# Brain-PCB_Master_RigFlex-test.net
KiCad netlist of a schematic drawn in Altium Designer
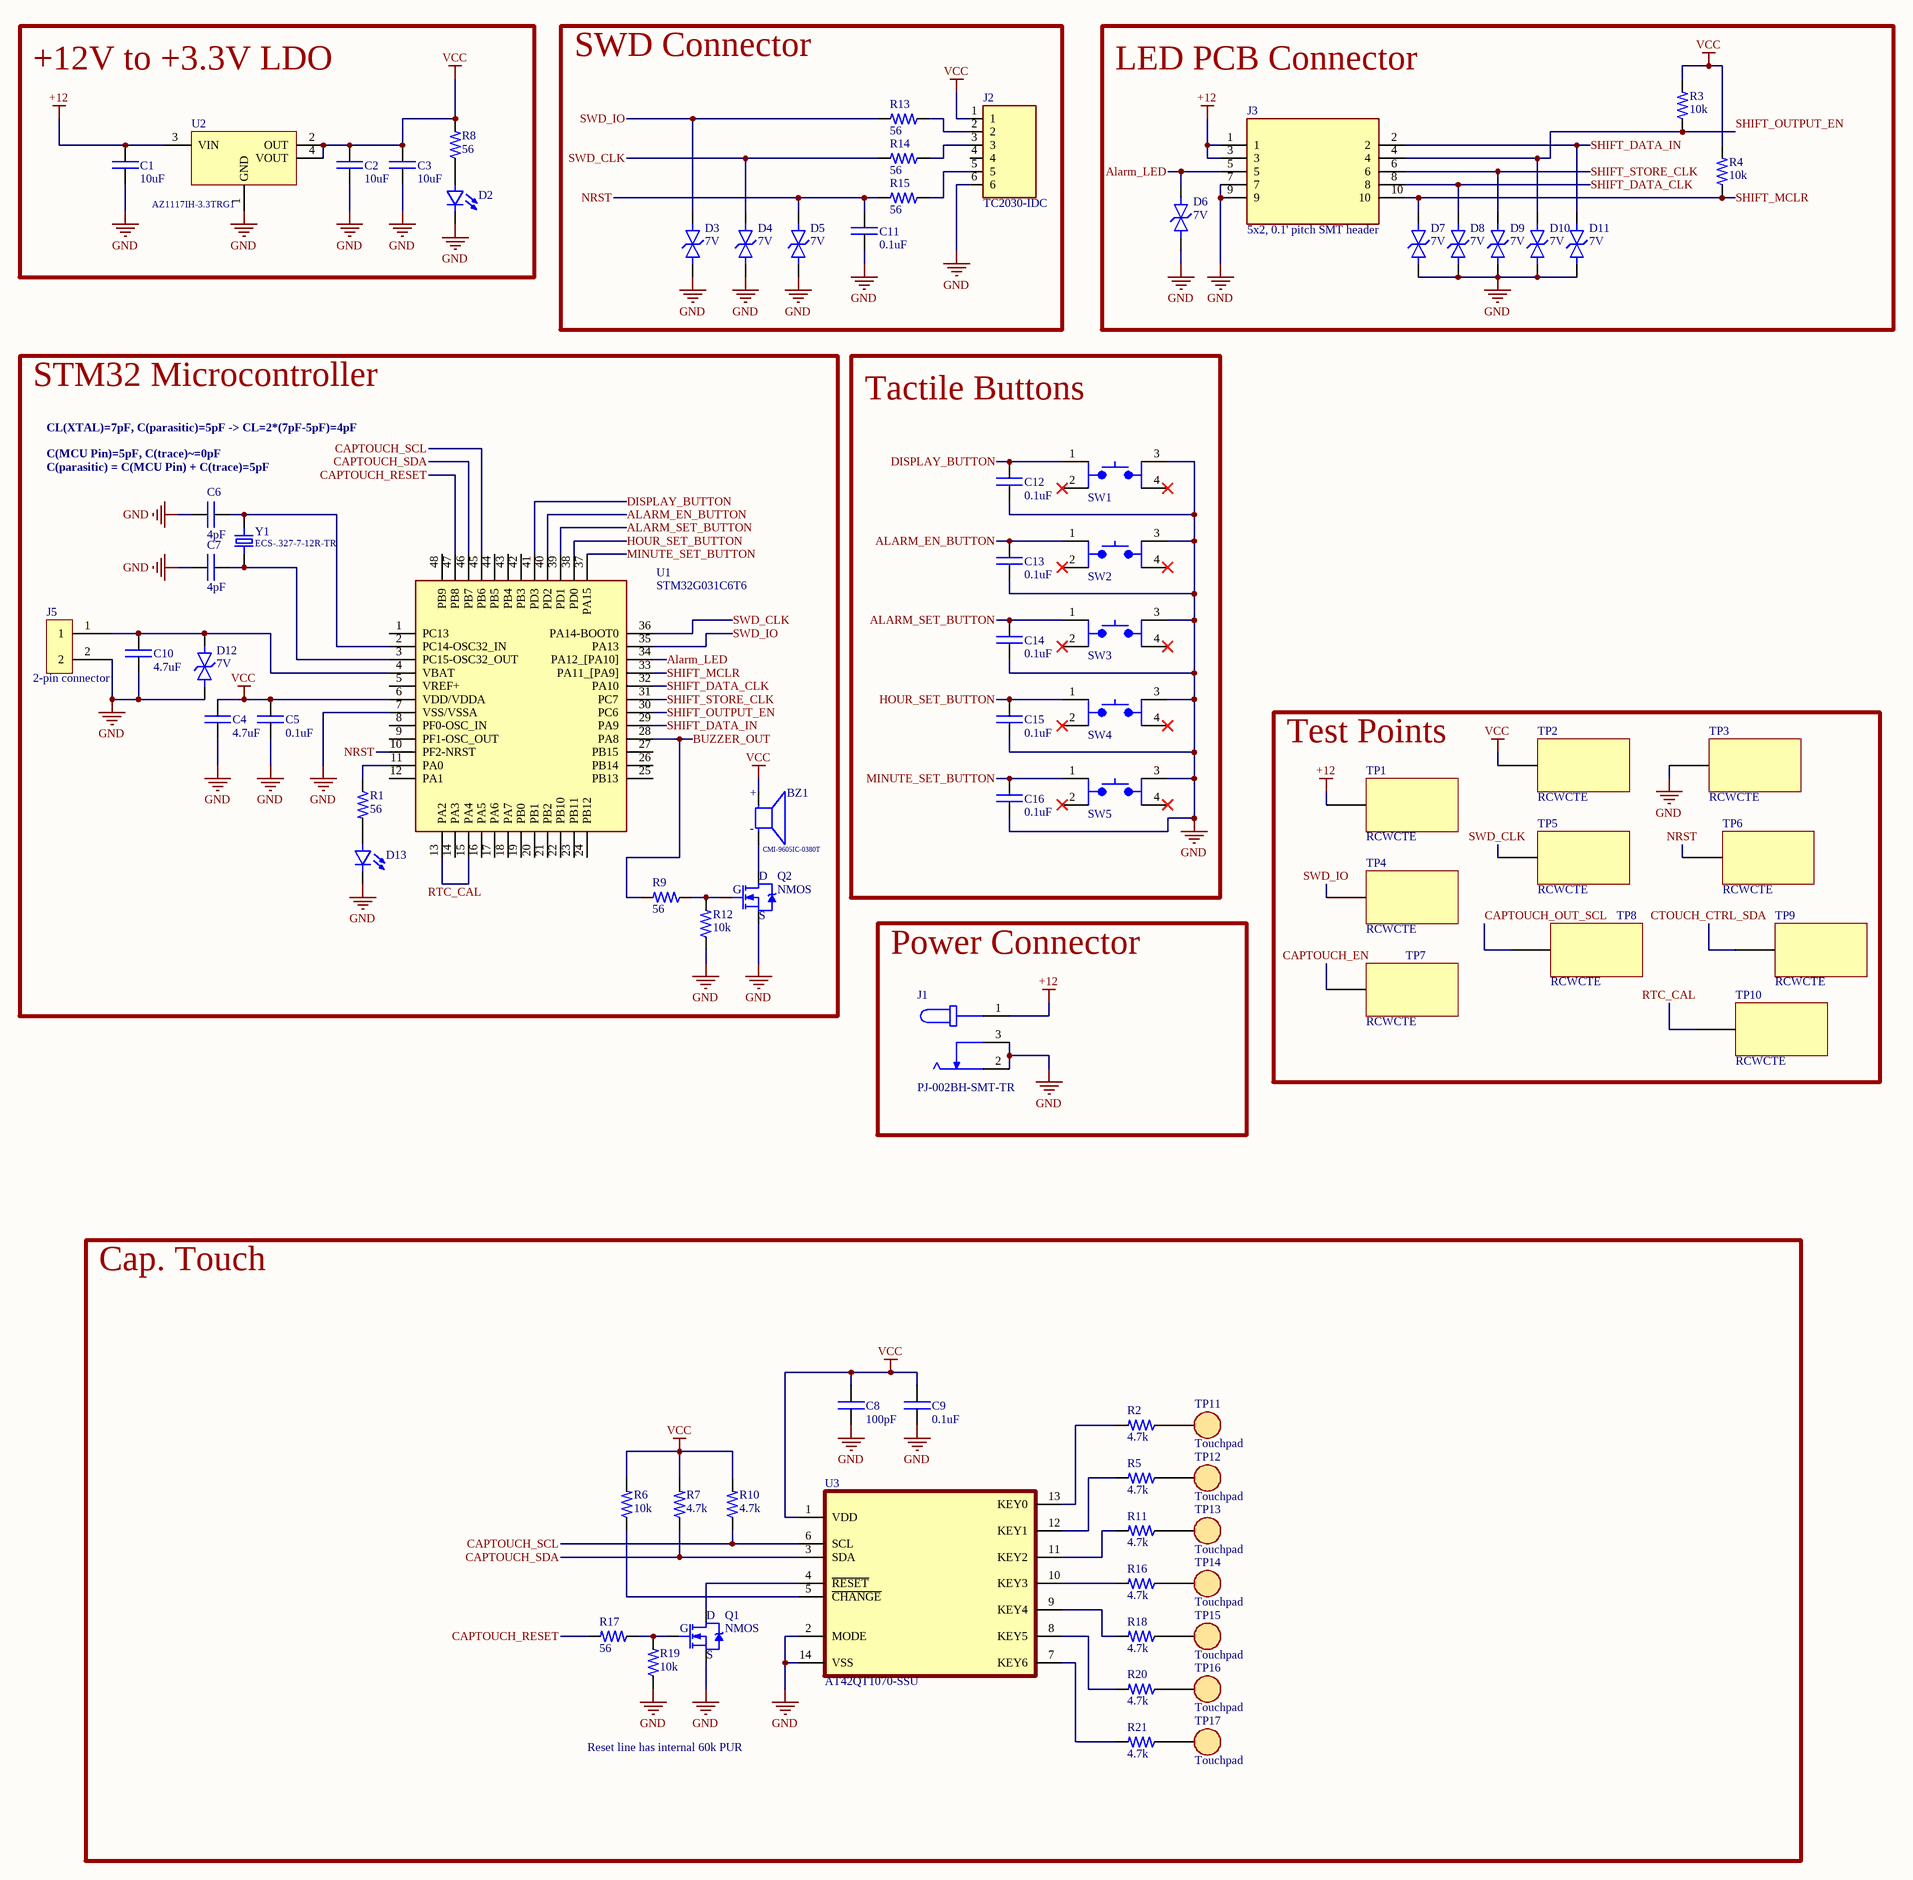
[diagram p0: Brain-PCB_Master_RigFlex-test.SchDoc]

(export (version "E")
  (design (tool "Eeschema 10.0.6"))
  (components
    (comp (ref "BZ1")
      (value "CMI-9605IC-0380T")
      (footprint "sinking-clock:CUI_CMI-9605IC-0380T")
      (description "MAGNETIC BUZZER INDICATOR")
      (fields (field (name "MFR") "CUI Devices"))
      (libsource (lib "sinking-clock") (part "CMI-9605IC-0380T"))
    )
    (comp (ref "C1")
      (value "10uF")
      (footprint "sinking-clock:0402C")
      (description "Capaicitor")
      (fields (field (name "MFR") "KYOCERA AVX") (field (name "Comment") "CAP"))
      (libsource (lib "sinking-clock") (part "CAP"))
    )
    (comp (ref "C2")
      (value "10uF")
      (footprint "sinking-clock:0402C")
      (description "Capaicitor")
      (fields (field (name "MFR") "KYOCERA AVX") (field (name "Comment") "CAP"))
      (libsource (lib "sinking-clock") (part "CAP"))
    )
    (comp (ref "C3")
      (value "10uF")
      (footprint "sinking-clock:0402C")
      (description "Capaicitor")
      (fields (field (name "MFR") "KYOCERA AVX") (field (name "Comment") "CAP"))
      (libsource (lib "sinking-clock") (part "CAP"))
    )
    (comp (ref "C4")
      (value "4.7uF")
      (footprint "sinking-clock:0402C")
      (description "Capaicitor")
      (fields (field (name "MFR") "Samsung Electro-Mechanics") (field (name "Comment") "CAP"))
      (libsource (lib "sinking-clock") (part "CAP"))
    )
    (comp (ref "C5")
      (value "0.1uF")
      (footprint "sinking-clock:0402C")
      (description "Capaicitor")
      (fields (field (name "MFR") "Samsung Electro-Mechanics") (field (name "Comment") "CAP"))
      (libsource (lib "sinking-clock") (part "CAP"))
    )
    (comp (ref "C6")
      (value "4pF")
      (footprint "sinking-clock:0402C")
      (description "Capaicitor")
      (fields (field (name "Comment") "CAP"))
      (libsource (lib "sinking-clock") (part "CAP"))
    )
    (comp (ref "C7")
      (value "4pF")
      (footprint "sinking-clock:0402C")
      (description "Capaicitor")
      (fields (field (name "Comment") "CAP"))
      (libsource (lib "sinking-clock") (part "CAP"))
    )
    (comp (ref "C8")
      (value "100pF")
      (footprint "sinking-clock:0402C")
      (description "Capaicitor")
      (fields (field (name "Comment") "CAP"))
      (libsource (lib "sinking-clock") (part "CAP"))
    )
    (comp (ref "C9")
      (value "0.1uF")
      (footprint "sinking-clock:0402C")
      (description "Capaicitor")
      (fields (field (name "MFR") "Samsung Electro-Mechanics") (field (name "Comment") "CAP"))
      (libsource (lib "sinking-clock") (part "CAP"))
    )
    (comp (ref "C10")
      (value "4.7uF")
      (footprint "sinking-clock:0402C")
      (description "Capaicitor")
      (fields (field (name "MFR") "Samsung Electro-Mechanics") (field (name "Comment") "CAP"))
      (libsource (lib "sinking-clock") (part "CAP"))
    )
    (comp (ref "C11")
      (value "0.1uF")
      (footprint "sinking-clock:0402C")
      (description "Capaicitor")
      (fields (field (name "MFR") "Samsung Electro-Mechanics") (field (name "Comment") "CAP"))
      (libsource (lib "sinking-clock") (part "CAP"))
    )
    (comp (ref "C12")
      (value "0.1uF")
      (footprint "sinking-clock:0402C")
      (description "Capaicitor")
      (fields (field (name "MFR") "Samsung Electro-Mechanics") (field (name "Comment") "CAP"))
      (libsource (lib "sinking-clock") (part "CAP"))
    )
    (comp (ref "C13")
      (value "0.1uF")
      (footprint "sinking-clock:0402C")
      (description "Capaicitor")
      (fields (field (name "MFR") "Samsung Electro-Mechanics") (field (name "Comment") "CAP"))
      (libsource (lib "sinking-clock") (part "CAP"))
    )
    (comp (ref "C14")
      (value "0.1uF")
      (footprint "sinking-clock:0402C")
      (description "Capaicitor")
      (fields (field (name "MFR") "Samsung Electro-Mechanics") (field (name "Comment") "CAP"))
      (libsource (lib "sinking-clock") (part "CAP"))
    )
    (comp (ref "C15")
      (value "0.1uF")
      (footprint "sinking-clock:0402C")
      (description "Capaicitor")
      (fields (field (name "MFR") "Samsung Electro-Mechanics") (field (name "Comment") "CAP"))
      (libsource (lib "sinking-clock") (part "CAP"))
    )
    (comp (ref "C16")
      (value "0.1uF")
      (footprint "sinking-clock:0402C")
      (description "Capaicitor")
      (fields (field (name "MFR") "Samsung Electro-Mechanics") (field (name "Comment") "CAP"))
      (libsource (lib "sinking-clock") (part "CAP"))
    )
    (comp (ref "D2")
      (value "LED - single")
      (footprint "sinking-clock:LED - 0603")
      (description "LED")
      (fields (field (name "MFR") "Dialight"))
      (libsource (lib "sinking-clock") (part "LED - single"))
    )
    (comp (ref "D3")
      (value "7V")
      (footprint "sinking-clock:DESD3V3S1BL-7B")
      (fields (field (name "MFR") "Diodes Incorporated"))
      (libsource (lib "sinking-clock") (part "TVS Diode Bi"))
    )
    (comp (ref "D4")
      (value "7V")
      (footprint "sinking-clock:DESD3V3S1BL-7B")
      (fields (field (name "MFR") "Diodes Incorporated"))
      (libsource (lib "sinking-clock") (part "TVS Diode Bi"))
    )
    (comp (ref "D5")
      (value "7V")
      (footprint "sinking-clock:DESD3V3S1BL-7B")
      (fields (field (name "MFR") "Diodes Incorporated"))
      (libsource (lib "sinking-clock") (part "TVS Diode Bi"))
    )
    (comp (ref "D6")
      (value "7V")
      (footprint "sinking-clock:DESD3V3S1BL-7B")
      (fields (field (name "MFR") "Diodes Incorporated"))
      (libsource (lib "sinking-clock") (part "TVS Diode Bi"))
    )
    (comp (ref "D7")
      (value "7V")
      (footprint "sinking-clock:DESD3V3S1BL-7B")
      (fields (field (name "MFR") "Diodes Incorporated"))
      (libsource (lib "sinking-clock") (part "TVS Diode Bi"))
    )
    (comp (ref "D8")
      (value "7V")
      (footprint "sinking-clock:DESD3V3S1BL-7B")
      (fields (field (name "MFR") "Diodes Incorporated"))
      (libsource (lib "sinking-clock") (part "TVS Diode Bi"))
    )
    (comp (ref "D9")
      (value "7V")
      (footprint "sinking-clock:DESD3V3S1BL-7B")
      (fields (field (name "MFR") "Diodes Incorporated"))
      (libsource (lib "sinking-clock") (part "TVS Diode Bi"))
    )
    (comp (ref "D10")
      (value "7V")
      (footprint "sinking-clock:DESD3V3S1BL-7B")
      (fields (field (name "MFR") "Diodes Incorporated"))
      (libsource (lib "sinking-clock") (part "TVS Diode Bi"))
    )
    (comp (ref "D11")
      (value "7V")
      (footprint "sinking-clock:DESD3V3S1BL-7B")
      (fields (field (name "MFR") "Diodes Incorporated"))
      (libsource (lib "sinking-clock") (part "TVS Diode Bi"))
    )
    (comp (ref "D12")
      (value "7V")
      (footprint "sinking-clock:DESD3V3S1BL-7B")
      (fields (field (name "MFR") "Diodes Incorporated"))
      (libsource (lib "sinking-clock") (part "TVS Diode Bi"))
    )
    (comp (ref "D13")
      (value "LED - single")
      (footprint "sinking-clock:LED - 0603")
      (description "LED")
      (fields (field (name "MFR") "Dialight"))
      (libsource (lib "sinking-clock") (part "LED - single"))
    )
    (comp (ref "J1")
      (value "PJ-002BH-SMT-TR")
      (footprint "sinking-clock:PJ-002BH-SMT-TR")
      (description "2.5 mm Center Pin, 5.0 A, Right Angle, Surface Mount (SMT), Dc Power Jack Connector")
      (fields (field (name "MFR") "CUI Devices"))
      (libsource (lib "sinking-clock") (part "PJ-002BH-SMT-TR"))
    )
    (comp (ref "J2")
      (value "TC2030-IDC")
      (footprint "sinking-clock:TAG CONNECT TC2030IDC - NO 3D MODEL")
      (description "\"Plug of Nails\" POGO Pin connector")
      (fields (field (name "MFR") "Tag-Connect"))
      (libsource (lib "sinking-clock") (part "TC2030-IDC"))
    )
    (comp (ref "J3")
      (value "5x2, 0.1' pitch SMT header")
      (footprint "sinking-clock:5x2, 0.1' pitch SMT header")
      (description "CONN HEADER SMD 10POS 2.54MM")
      (fields (field (name "MFR") "CNC Tech"))
      (libsource (lib "sinking-clock") (part "5x2, 0.1' pitch SMT header"))
    )
    (comp (ref "J5")
      (value "2-pin connector")
      (footprint "sinking-clock:2-pos, 0.1\" TH header")
      (description "2-pos connector, 0.1\", TH, male")
      (libsource (lib "sinking-clock") (part "2-pin connector"))
    )
    (comp (ref "Q1")
      (value "NMOS")
      (footprint "sinking-clock:SOT-23")
      (description "N-Channel MOSFET")
      (fields (field (name "MFR") "Diodes Incorporated"))
      (libsource (lib "sinking-clock") (part "NMOS"))
    )
    (comp (ref "Q2")
      (value "NMOS")
      (footprint "sinking-clock:SOT-23")
      (description "N-Channel MOSFET")
      (fields (field (name "MFR") "Diodes Incorporated"))
      (libsource (lib "sinking-clock") (part "NMOS"))
    )
    (comp (ref "R1")
      (value "56")
      (footprint "sinking-clock:0402R")
      (description "Resistor")
      (fields (field (name "MFR") "YAGEO") (field (name "Comment") "RES"))
      (libsource (lib "sinking-clock") (part "RES"))
    )
    (comp (ref "R2")
      (value "4.7k")
      (footprint "sinking-clock:0402R")
      (description "Resistor")
      (fields (field (name "MFR") "YAGEO") (field (name "Comment") "RES"))
      (libsource (lib "sinking-clock") (part "RES"))
    )
    (comp (ref "R3")
      (value "10k")
      (footprint "sinking-clock:0402R")
      (description "Resistor")
      (fields (field (name "MFR") "YAGEO") (field (name "Comment") "RES"))
      (libsource (lib "sinking-clock") (part "RES"))
    )
    (comp (ref "R4")
      (value "10k")
      (footprint "sinking-clock:0402R")
      (description "Resistor")
      (fields (field (name "MFR") "YAGEO") (field (name "Comment") "RES"))
      (libsource (lib "sinking-clock") (part "RES"))
    )
    (comp (ref "R5")
      (value "4.7k")
      (footprint "sinking-clock:0402R")
      (description "Resistor")
      (fields (field (name "MFR") "YAGEO") (field (name "Comment") "RES"))
      (libsource (lib "sinking-clock") (part "RES"))
    )
    (comp (ref "R6")
      (value "10k")
      (footprint "sinking-clock:0402R")
      (description "Resistor")
      (fields (field (name "MFR") "YAGEO") (field (name "Comment") "RES"))
      (libsource (lib "sinking-clock") (part "RES"))
    )
    (comp (ref "R7")
      (value "4.7k")
      (footprint "sinking-clock:0402R")
      (description "Resistor")
      (fields (field (name "MFR") "YAGEO") (field (name "Comment") "RES"))
      (libsource (lib "sinking-clock") (part "RES"))
    )
    (comp (ref "R8")
      (value "56")
      (footprint "sinking-clock:0402R")
      (description "Resistor")
      (fields (field (name "MFR") "YAGEO") (field (name "Comment") "RES"))
      (libsource (lib "sinking-clock") (part "RES"))
    )
    (comp (ref "R9")
      (value "56")
      (footprint "sinking-clock:0402R")
      (description "Resistor")
      (fields (field (name "MFR") "YAGEO") (field (name "Comment") "RES"))
      (libsource (lib "sinking-clock") (part "RES"))
    )
    (comp (ref "R10")
      (value "4.7k")
      (footprint "sinking-clock:0402R")
      (description "Resistor")
      (fields (field (name "MFR") "YAGEO") (field (name "Comment") "RES"))
      (libsource (lib "sinking-clock") (part "RES"))
    )
    (comp (ref "R11")
      (value "4.7k")
      (footprint "sinking-clock:0402R")
      (description "Resistor")
      (fields (field (name "MFR") "YAGEO") (field (name "Comment") "RES"))
      (libsource (lib "sinking-clock") (part "RES"))
    )
    (comp (ref "R12")
      (value "10k")
      (footprint "sinking-clock:0402R")
      (description "Resistor")
      (fields (field (name "MFR") "YAGEO") (field (name "Comment") "RES"))
      (libsource (lib "sinking-clock") (part "RES"))
    )
    (comp (ref "R13")
      (value "56")
      (footprint "sinking-clock:0402R")
      (description "Resistor")
      (fields (field (name "MFR") "YAGEO") (field (name "Comment") "RES"))
      (libsource (lib "sinking-clock") (part "RES"))
    )
    (comp (ref "R14")
      (value "56")
      (footprint "sinking-clock:0402R")
      (description "Resistor")
      (fields (field (name "MFR") "YAGEO") (field (name "Comment") "RES"))
      (libsource (lib "sinking-clock") (part "RES"))
    )
    (comp (ref "R15")
      (value "56")
      (footprint "sinking-clock:0402R")
      (description "Resistor")
      (fields (field (name "MFR") "YAGEO") (field (name "Comment") "RES"))
      (libsource (lib "sinking-clock") (part "RES"))
    )
    (comp (ref "R16")
      (value "4.7k")
      (footprint "sinking-clock:0402R")
      (description "Resistor")
      (fields (field (name "MFR") "YAGEO") (field (name "Comment") "RES"))
      (libsource (lib "sinking-clock") (part "RES"))
    )
    (comp (ref "R17")
      (value "56")
      (footprint "sinking-clock:0402R")
      (description "Resistor")
      (fields (field (name "MFR") "YAGEO") (field (name "Comment") "RES"))
      (libsource (lib "sinking-clock") (part "RES"))
    )
    (comp (ref "R18")
      (value "4.7k")
      (footprint "sinking-clock:0402R")
      (description "Resistor")
      (fields (field (name "MFR") "YAGEO") (field (name "Comment") "RES"))
      (libsource (lib "sinking-clock") (part "RES"))
    )
    (comp (ref "R19")
      (value "10k")
      (footprint "sinking-clock:0402R")
      (description "Resistor")
      (fields (field (name "MFR") "YAGEO") (field (name "Comment") "RES"))
      (libsource (lib "sinking-clock") (part "RES"))
    )
    (comp (ref "R20")
      (value "4.7k")
      (footprint "sinking-clock:0402R")
      (description "Resistor")
      (fields (field (name "MFR") "YAGEO") (field (name "Comment") "RES"))
      (libsource (lib "sinking-clock") (part "RES"))
    )
    (comp (ref "R21")
      (value "4.7k")
      (footprint "sinking-clock:0402R")
      (description "Resistor")
      (fields (field (name "MFR") "YAGEO") (field (name "Comment") "RES"))
      (libsource (lib "sinking-clock") (part "RES"))
    )
    (comp (ref "SW1")
      (value "SPDT SMT Tactile Push Button Switch")
      (footprint "sinking-clock:TL3301BF160QGTUBE")
      (description "Tactile Push Button Switch, Gull Wing Lead, 9.5mm contact height")
      (fields (field (name "MFR") "E-Switch"))
      (libsource (lib "sinking-clock") (part "SPDT SMT Tactile Push Button Switch"))
    )
    (comp (ref "SW2")
      (value "SPDT SMT Tactile Push Button Switch")
      (footprint "sinking-clock:TL3301BF160QGTUBE")
      (description "Tactile Push Button Switch, Gull Wing Lead, 9.5mm contact height")
      (fields (field (name "MFR") "E-Switch"))
      (libsource (lib "sinking-clock") (part "SPDT SMT Tactile Push Button Switch"))
    )
    (comp (ref "SW3")
      (value "SPDT SMT Tactile Push Button Switch")
      (footprint "sinking-clock:TL3301BF160QGTUBE")
      (description "Tactile Push Button Switch, Gull Wing Lead, 9.5mm contact height")
      (fields (field (name "MFR") "E-Switch"))
      (libsource (lib "sinking-clock") (part "SPDT SMT Tactile Push Button Switch"))
    )
    (comp (ref "SW4")
      (value "SPDT SMT Tactile Push Button Switch")
      (footprint "sinking-clock:TL3301BF160QGTUBE")
      (description "Tactile Push Button Switch, Gull Wing Lead, 9.5mm contact height")
      (fields (field (name "MFR") "E-Switch"))
      (libsource (lib "sinking-clock") (part "SPDT SMT Tactile Push Button Switch"))
    )
    (comp (ref "SW5")
      (value "SPDT SMT Tactile Push Button Switch")
      (footprint "sinking-clock:TL3301BF160QGTUBE")
      (description "Tactile Push Button Switch, Gull Wing Lead, 9.5mm contact height")
      (fields (field (name "MFR") "E-Switch"))
      (libsource (lib "sinking-clock") (part "SPDT SMT Tactile Push Button Switch"))
    )
    (comp (ref "TP1")
      (value "RCWCTE")
      (footprint "sinking-clock:RCWCTE")
      (description "Test Point, Surface Mount")
      (fields (field (name "MFR") "KOA Speer Electronics, Inc."))
      (libsource (lib "sinking-clock") (part "Test Point"))
    )
    (comp (ref "TP2")
      (value "RCWCTE")
      (footprint "sinking-clock:RCWCTE")
      (description "Test Point, Surface Mount")
      (fields (field (name "MFR") "KOA Speer Electronics, Inc."))
      (libsource (lib "sinking-clock") (part "Test Point"))
    )
    (comp (ref "TP3")
      (value "RCWCTE")
      (footprint "sinking-clock:RCWCTE")
      (description "Test Point, Surface Mount")
      (fields (field (name "MFR") "KOA Speer Electronics, Inc."))
      (libsource (lib "sinking-clock") (part "Test Point"))
    )
    (comp (ref "TP4")
      (value "RCWCTE")
      (footprint "sinking-clock:RCWCTE")
      (description "Test Point, Surface Mount")
      (fields (field (name "MFR") "KOA Speer Electronics, Inc."))
      (libsource (lib "sinking-clock") (part "Test Point"))
    )
    (comp (ref "TP5")
      (value "RCWCTE")
      (footprint "sinking-clock:RCWCTE")
      (description "Test Point, Surface Mount")
      (fields (field (name "MFR") "KOA Speer Electronics, Inc."))
      (libsource (lib "sinking-clock") (part "Test Point"))
    )
    (comp (ref "TP6")
      (value "RCWCTE")
      (footprint "sinking-clock:RCWCTE")
      (description "Test Point, Surface Mount")
      (fields (field (name "MFR") "KOA Speer Electronics, Inc."))
      (libsource (lib "sinking-clock") (part "Test Point"))
    )
    (comp (ref "TP7")
      (value "RCWCTE")
      (footprint "sinking-clock:RCWCTE")
      (description "Test Point, Surface Mount")
      (fields (field (name "MFR") "KOA Speer Electronics, Inc."))
      (libsource (lib "sinking-clock") (part "Test Point"))
    )
    (comp (ref "TP8")
      (value "RCWCTE")
      (footprint "sinking-clock:RCWCTE")
      (description "Test Point, Surface Mount")
      (fields (field (name "MFR") "KOA Speer Electronics, Inc."))
      (libsource (lib "sinking-clock") (part "Test Point"))
    )
    (comp (ref "TP9")
      (value "RCWCTE")
      (footprint "sinking-clock:RCWCTE")
      (description "Test Point, Surface Mount")
      (fields (field (name "MFR") "KOA Speer Electronics, Inc."))
      (libsource (lib "sinking-clock") (part "Test Point"))
    )
    (comp (ref "TP10")
      (value "RCWCTE")
      (footprint "sinking-clock:RCWCTE")
      (description "Test Point, Surface Mount")
      (fields (field (name "MFR") "KOA Speer Electronics, Inc."))
      (libsource (lib "sinking-clock") (part "Test Point"))
    )
    (comp (ref "TP11") (value "Touchpad") (libsource (lib "sinking-clock") (part "Touchpad")))
    (comp (ref "TP12") (value "Touchpad") (libsource (lib "sinking-clock") (part "Touchpad")))
    (comp (ref "TP13") (value "Touchpad") (libsource (lib "sinking-clock") (part "Touchpad")))
    (comp (ref "TP14") (value "Touchpad") (libsource (lib "sinking-clock") (part "Touchpad")))
    (comp (ref "TP15") (value "Touchpad") (libsource (lib "sinking-clock") (part "Touchpad")))
    (comp (ref "TP16") (value "Touchpad") (libsource (lib "sinking-clock") (part "Touchpad")))
    (comp (ref "TP17") (value "Touchpad") (libsource (lib "sinking-clock") (part "Touchpad")))
    (comp (ref "U1")
      (value "STM32G031C6T6")
      (footprint "sinking-clock:48-LQFP")
      (fields (field (name "MFR") "STMicroelectronics"))
      (libsource (lib "sinking-clock") (part "STM32G031C6T6"))
    )
    (comp (ref "U2")
      (value "AZ1117IH-3.3TRG1")
      (footprint "sinking-clock:SOT-223-3")
      (description "IC REG LINEAR 3.3V 1A SOT223")
      (fields (field (name "MFR") "Diodes Incorporated"))
      (libsource (lib "sinking-clock") (part "AZ1117IH-3.3TRG1"))
    )
    (comp (ref "U3")
      (value "AT42QT1070-SSU")
      (footprint "sinking-clock:14-SOIC")
      (description "Capacitive Touch Buttons 14-SOIC")
      (fields (field (name "MFR") "Microchip"))
      (libsource (lib "sinking-clock") (part "AT42QT1070-SSU"))
    )
    (comp (ref "Y1")
      (value "ECS-.327-7-12R-TR")
      (footprint "sinking-clock:ECS-.327-12.5-12R-TR")
      (description "SMD Tuning Fork Crystal")
      (fields (field (name "MFR") "ECS Inc."))
      (libsource (lib "sinking-clock") (part "ECS-.327-7-12R-TR"))
    )
  )
  (nets
    (net (code "1") (name "+12") (class "Default")
      (node (ref "C1") (pin "2") (pinfunction "2_2") (pintype "passive"))
      (node (ref "J1") (pin "1") (pinfunction "1_1") (pintype "passive"))
      (node (ref "J3") (pin "1") (pinfunction "1_1") (pintype "passive"))
      (node (ref "J3") (pin "3") (pinfunction "3_3") (pintype "passive"))
      (node (ref "TP1") (pin "1") (pinfunction "0_1") (pintype "passive"))
      (node (ref "U2") (pin "3") (pinfunction "VIN_3") (pintype "passive"))
    )
    (net (code "2") (name "/ALARM_EN_BUTTON") (class "Default")
      (node (ref "C13") (pin "2") (pinfunction "2_2") (pintype "passive"))
      (node (ref "SW2") (pin "1") (pinfunction "1_1") (pintype "passive"))
      (node (ref "U1") (pin "40") (pinfunction "PD2_40") (pintype "passive"))
    )
    (net (code "3") (name "/ALARM_SET_BUTTON") (class "Default")
      (node (ref "C14") (pin "2") (pinfunction "2_2") (pintype "passive"))
      (node (ref "SW3") (pin "1") (pinfunction "1_1") (pintype "passive"))
      (node (ref "U1") (pin "39") (pinfunction "PD1_39") (pintype "passive"))
    )
    (net (code "4") (name "/Alarm_LED") (class "Default")
      (node (ref "D6") (pin "1") (pinfunction "1_1") (pintype "passive"))
      (node (ref "J3") (pin "5") (pinfunction "5_5") (pintype "passive"))
      (node (ref "U1") (pin "34") (pinfunction "PA12_[PA10]_34") (pintype "passive"))
    )
    (net (code "5") (name "/BUZZER_OUT") (class "Default")
      (node (ref "R9") (pin "2") (pinfunction "2_2") (pintype "passive"))
      (node (ref "U1") (pin "28") (pinfunction "PA8_28") (pintype "passive"))
    )
    (net (code "6") (name "/CAPTOUCH_EN") (class "Default")
      (node (ref "TP7") (pin "1") (pinfunction "0_1") (pintype "passive"))
    )
    (net (code "7") (name "/CAPTOUCH_OUT_SCL") (class "Default")
      (node (ref "TP8") (pin "1") (pinfunction "0_1") (pintype "passive"))
    )
    (net (code "8") (name "/CAPTOUCH_RESET") (class "Default")
      (node (ref "R17") (pin "2") (pinfunction "2_2") (pintype "passive"))
      (node (ref "U1") (pin "47") (pinfunction "PB8_47") (pintype "passive"))
    )
    (net (code "9") (name "/CAPTOUCH_SCL") (class "Default")
      (node (ref "R10") (pin "1") (pinfunction "1_1") (pintype "passive"))
      (node (ref "U1") (pin "45") (pinfunction "PB6_45") (pintype "passive"))
      (node (ref "U3") (pin "6") (pinfunction "SCL_6") (pintype "passive"))
    )
    (net (code "10") (name "/CAPTOUCH_SDA") (class "Default")
      (node (ref "R7") (pin "1") (pinfunction "1_1") (pintype "passive"))
      (node (ref "U1") (pin "46") (pinfunction "PB7_46") (pintype "passive"))
      (node (ref "U3") (pin "3") (pinfunction "SDA_3") (pintype "passive"))
    )
    (net (code "11") (name "/CTOUCH_CTRL_SDA") (class "Default")
      (node (ref "TP9") (pin "1") (pinfunction "0_1") (pintype "passive"))
    )
    (net (code "12") (name "/DISPLAY_BUTTON") (class "Default")
      (node (ref "C12") (pin "2") (pinfunction "2_2") (pintype "passive"))
      (node (ref "SW1") (pin "1") (pinfunction "1_1") (pintype "passive"))
      (node (ref "U1") (pin "41") (pinfunction "PD3_41") (pintype "passive"))
    )
    (net (code "13") (name "/HOUR_SET_BUTTON") (class "Default")
      (node (ref "C15") (pin "2") (pinfunction "2_2") (pintype "passive"))
      (node (ref "SW4") (pin "1") (pinfunction "1_1") (pintype "passive"))
      (node (ref "U1") (pin "38") (pinfunction "PD0_38") (pintype "passive"))
    )
    (net (code "14") (name "/MINUTE_SET_BUTTON") (class "Default")
      (node (ref "C16") (pin "2") (pinfunction "2_2") (pintype "passive"))
      (node (ref "SW5") (pin "1") (pinfunction "1_1") (pintype "passive"))
      (node (ref "U1") (pin "37") (pinfunction "PA15_37") (pintype "passive"))
    )
    (net (code "15") (name "/NRST") (class "Default")
      (node (ref "C11") (pin "2") (pinfunction "2_2") (pintype "passive"))
      (node (ref "D5") (pin "1") (pinfunction "1_1") (pintype "passive"))
      (node (ref "R15") (pin "2") (pinfunction "2_2") (pintype "passive"))
      (node (ref "TP6") (pin "1") (pinfunction "0_1") (pintype "passive"))
      (node (ref "U1") (pin "10") (pinfunction "PF2-NRST_10") (pintype "passive"))
    )
    (net (code "16") (name "/RTC_CAL") (class "Default")
      (node (ref "TP10") (pin "1") (pinfunction "0_1") (pintype "passive"))
      (node (ref "U1") (pin "13") (pinfunction "PA2_13") (pintype "passive"))
      (node (ref "U1") (pin "15") (pinfunction "PA4_15") (pintype "passive"))
    )
    (net (code "17") (name "/SHIFT_DATA_CLK") (class "Default")
      (node (ref "D8") (pin "1") (pinfunction "1_1") (pintype "passive"))
      (node (ref "J3") (pin "8") (pinfunction "8_8") (pintype "passive"))
      (node (ref "U1") (pin "32") (pinfunction "PA10_32") (pintype "passive"))
    )
    (net (code "18") (name "/SHIFT_DATA_IN") (class "Default")
      (node (ref "D11") (pin "1") (pinfunction "1_1") (pintype "passive"))
      (node (ref "J3") (pin "2") (pinfunction "2_2") (pintype "passive"))
      (node (ref "U1") (pin "29") (pinfunction "PA9_29") (pintype "passive"))
    )
    (net (code "19") (name "/SHIFT_MCLR") (class "Default")
      (node (ref "D7") (pin "1") (pinfunction "1_1") (pintype "passive"))
      (node (ref "J3") (pin "10") (pinfunction "10_10") (pintype "passive"))
      (node (ref "R4") (pin "1") (pinfunction "1_1") (pintype "passive"))
      (node (ref "U1") (pin "33") (pinfunction "PA11_[PA9]_33") (pintype "passive"))
    )
    (net (code "20") (name "/SHIFT_OUTPUT_EN") (class "Default")
      (node (ref "D10") (pin "1") (pinfunction "1_1") (pintype "passive"))
      (node (ref "J3") (pin "4") (pinfunction "4_4") (pintype "passive"))
      (node (ref "R3") (pin "1") (pinfunction "1_1") (pintype "passive"))
      (node (ref "U1") (pin "30") (pinfunction "PC6_30") (pintype "passive"))
    )
    (net (code "21") (name "/SHIFT_STORE_CLK") (class "Default")
      (node (ref "D9") (pin "1") (pinfunction "1_1") (pintype "passive"))
      (node (ref "J3") (pin "6") (pinfunction "6_6") (pintype "passive"))
      (node (ref "U1") (pin "31") (pinfunction "PC7_31") (pintype "passive"))
    )
    (net (code "22") (name "/SWD_CLK") (class "Default")
      (node (ref "D4") (pin "1") (pinfunction "1_1") (pintype "passive"))
      (node (ref "R14") (pin "2") (pinfunction "2_2") (pintype "passive"))
      (node (ref "TP5") (pin "1") (pinfunction "0_1") (pintype "passive"))
      (node (ref "U1") (pin "36") (pinfunction "PA14-BOOT0_36") (pintype "passive"))
    )
    (net (code "23") (name "/SWD_IO") (class "Default")
      (node (ref "D3") (pin "1") (pinfunction "1_1") (pintype "passive"))
      (node (ref "R13") (pin "2") (pinfunction "2_2") (pintype "passive"))
      (node (ref "TP4") (pin "1") (pinfunction "0_1") (pintype "passive"))
      (node (ref "U1") (pin "35") (pinfunction "PA13_35") (pintype "passive"))
    )
    (net (code "24") (name "GND") (class "Default")
      (node (ref "C1") (pin "1") (pinfunction "1_1") (pintype "passive"))
      (node (ref "C10") (pin "1") (pinfunction "1_1") (pintype "passive"))
      (node (ref "C11") (pin "1") (pinfunction "1_1") (pintype "passive"))
      (node (ref "C12") (pin "1") (pinfunction "1_1") (pintype "passive"))
      (node (ref "C13") (pin "1") (pinfunction "1_1") (pintype "passive"))
      (node (ref "C14") (pin "1") (pinfunction "1_1") (pintype "passive"))
      (node (ref "C15") (pin "1") (pinfunction "1_1") (pintype "passive"))
      (node (ref "C16") (pin "1") (pinfunction "1_1") (pintype "passive"))
      (node (ref "C2") (pin "1") (pinfunction "1_1") (pintype "passive"))
      (node (ref "C3") (pin "1") (pinfunction "1_1") (pintype "passive"))
      (node (ref "C4") (pin "1") (pinfunction "1_1") (pintype "passive"))
      (node (ref "C5") (pin "1") (pinfunction "1_1") (pintype "passive"))
      (node (ref "C6") (pin "1") (pinfunction "1_1") (pintype "passive"))
      (node (ref "C7") (pin "1") (pinfunction "1_1") (pintype "passive"))
      (node (ref "C8") (pin "1") (pinfunction "1_1") (pintype "passive"))
      (node (ref "C9") (pin "1") (pinfunction "1_1") (pintype "passive"))
      (node (ref "D10") (pin "2") (pinfunction "2_2") (pintype "passive"))
      (node (ref "D11") (pin "2") (pinfunction "2_2") (pintype "passive"))
      (node (ref "D12") (pin "2") (pinfunction "2_2") (pintype "passive"))
      (node (ref "D13") (pin "2") (pinfunction "C_2") (pintype "passive"))
      (node (ref "D2") (pin "2") (pinfunction "C_2") (pintype "passive"))
      (node (ref "D3") (pin "2") (pinfunction "2_2") (pintype "passive"))
      (node (ref "D4") (pin "2") (pinfunction "2_2") (pintype "passive"))
      (node (ref "D5") (pin "2") (pinfunction "2_2") (pintype "passive"))
      (node (ref "D6") (pin "2") (pinfunction "2_2") (pintype "passive"))
      (node (ref "D7") (pin "2") (pinfunction "2_2") (pintype "passive"))
      (node (ref "D8") (pin "2") (pinfunction "2_2") (pintype "passive"))
      (node (ref "D9") (pin "2") (pinfunction "2_2") (pintype "passive"))
      (node (ref "J1") (pin "2") (pinfunction "2_2") (pintype "passive"))
      (node (ref "J1") (pin "3") (pinfunction "3_3") (pintype "passive"))
      (node (ref "J2") (pin "6") (pinfunction "6_6") (pintype "passive"))
      (node (ref "J3") (pin "7") (pinfunction "7_7") (pintype "passive"))
      (node (ref "J3") (pin "9") (pinfunction "9_9") (pintype "passive"))
      (node (ref "J5") (pin "2") (pinfunction "2_2") (pintype "passive"))
      (node (ref "Q1") (pin "2") (pinfunction "S_2") (pintype "passive"))
      (node (ref "Q2") (pin "2") (pinfunction "S_2") (pintype "passive"))
      (node (ref "R12") (pin "1") (pinfunction "1_1") (pintype "passive"))
      (node (ref "R19") (pin "1") (pinfunction "1_1") (pintype "passive"))
      (node (ref "SW1") (pin "3") (pinfunction "3_3") (pintype "passive"))
      (node (ref "SW2") (pin "3") (pinfunction "3_3") (pintype "passive"))
      (node (ref "SW3") (pin "3") (pinfunction "3_3") (pintype "passive"))
      (node (ref "SW4") (pin "3") (pinfunction "3_3") (pintype "passive"))
      (node (ref "SW5") (pin "3") (pinfunction "3_3") (pintype "passive"))
      (node (ref "TP3") (pin "1") (pinfunction "0_1") (pintype "passive"))
      (node (ref "U1") (pin "7") (pinfunction "VSS/VSSA_7") (pintype "passive"))
      (node (ref "U2") (pin "1") (pinfunction "GND_1") (pintype "passive"))
      (node (ref "U3") (pin "14") (pinfunction "VSS_14") (pintype "passive"))
      (node (ref "U3") (pin "2") (pinfunction "MODE_2") (pintype "passive"))
    )
    (net (code "25") (name "Net-(D2-A)") (class "Default")
      (node (ref "D2") (pin "1") (pinfunction "A_1") (pintype "passive"))
      (node (ref "R8") (pin "1") (pinfunction "1_1") (pintype "passive"))
    )
    (net (code "26") (name "Net-(D13-A)") (class "Default")
      (node (ref "D13") (pin "1") (pinfunction "A_1") (pintype "passive"))
      (node (ref "R1") (pin "2") (pinfunction "2_2") (pintype "passive"))
    )
    (net (code "27") (name "Net-(J2-Pad2)") (class "Default")
      (node (ref "J2") (pin "2") (pinfunction "2_2") (pintype "passive"))
      (node (ref "R13") (pin "1") (pinfunction "1_1") (pintype "passive"))
    )
    (net (code "28") (name "Net-(J2-Pad3)") (class "Default")
      (node (ref "J2") (pin "3") (pinfunction "3_3") (pintype "passive"))
      (node (ref "R14") (pin "1") (pinfunction "1_1") (pintype "passive"))
    )
    (net (code "29") (name "Net-(J2-Pad5)") (class "Default")
      (node (ref "J2") (pin "5") (pinfunction "5_5") (pintype "passive"))
      (node (ref "R15") (pin "1") (pinfunction "1_1") (pintype "passive"))
    )
    (net (code "30") (name "Net-(Q1-D)") (class "Default")
      (node (ref "Q1") (pin "3") (pinfunction "D_3") (pintype "passive"))
      (node (ref "U3") (pin "4") (pinfunction "~{RESET}_4") (pintype "passive"))
    )
    (net (code "31") (name "Net-(Q1-G)") (class "Default")
      (node (ref "Q1") (pin "1") (pinfunction "G_1") (pintype "passive"))
      (node (ref "R17") (pin "1") (pinfunction "1_1") (pintype "passive"))
      (node (ref "R19") (pin "2") (pinfunction "2_2") (pintype "passive"))
    )
    (net (code "32") (name "Net-(Q2-D)") (class "Default")
      (node (ref "BZ1") (pin "N") (pinfunction "N_N") (pintype "passive"))
      (node (ref "Q2") (pin "3") (pinfunction "D_3") (pintype "passive"))
    )
    (net (code "33") (name "Net-(Q2-G)") (class "Default")
      (node (ref "Q2") (pin "1") (pinfunction "G_1") (pintype "passive"))
      (node (ref "R12") (pin "2") (pinfunction "2_2") (pintype "passive"))
      (node (ref "R9") (pin "1") (pinfunction "1_1") (pintype "passive"))
    )
    (net (code "34") (name "Net-(TP11-0)") (class "Default")
      (node (ref "R2") (pin "1") (pinfunction "1_1") (pintype "passive"))
      (node (ref "TP11") (pin "1") (pinfunction "0_1") (pintype "passive"))
    )
    (net (code "35") (name "Net-(TP12-0)") (class "Default")
      (node (ref "R5") (pin "1") (pinfunction "1_1") (pintype "passive"))
      (node (ref "TP12") (pin "1") (pinfunction "0_1") (pintype "passive"))
    )
    (net (code "36") (name "Net-(TP13-0)") (class "Default")
      (node (ref "R11") (pin "1") (pinfunction "1_1") (pintype "passive"))
      (node (ref "TP13") (pin "1") (pinfunction "0_1") (pintype "passive"))
    )
    (net (code "37") (name "Net-(TP14-0)") (class "Default")
      (node (ref "R16") (pin "1") (pinfunction "1_1") (pintype "passive"))
      (node (ref "TP14") (pin "1") (pinfunction "0_1") (pintype "passive"))
    )
    (net (code "38") (name "Net-(TP15-0)") (class "Default")
      (node (ref "R18") (pin "1") (pinfunction "1_1") (pintype "passive"))
      (node (ref "TP15") (pin "1") (pinfunction "0_1") (pintype "passive"))
    )
    (net (code "39") (name "Net-(TP16-0)") (class "Default")
      (node (ref "R20") (pin "1") (pinfunction "1_1") (pintype "passive"))
      (node (ref "TP16") (pin "1") (pinfunction "0_1") (pintype "passive"))
    )
    (net (code "40") (name "Net-(TP17-0)") (class "Default")
      (node (ref "R21") (pin "1") (pinfunction "1_1") (pintype "passive"))
      (node (ref "TP17") (pin "1") (pinfunction "0_1") (pintype "passive"))
    )
    (net (code "41") (name "Net-(U1-PA0)") (class "Default")
      (node (ref "R1") (pin "1") (pinfunction "1_1") (pintype "passive"))
      (node (ref "U1") (pin "11") (pinfunction "PA0_11") (pintype "passive"))
    )
    (net (code "42") (name "Net-(U1-PC14-OSC32_IN)") (class "Default")
      (node (ref "C6") (pin "2") (pinfunction "2_2") (pintype "passive"))
      (node (ref "U1") (pin "2") (pinfunction "PC14-OSC32_IN_2") (pintype "passive"))
      (node (ref "Y1") (pin "2") (pinfunction "2_2") (pintype "passive"))
    )
    (net (code "43") (name "Net-(U1-PC15-OSC32_OUT)") (class "Default")
      (node (ref "C7") (pin "2") (pinfunction "2_2") (pintype "passive"))
      (node (ref "U1") (pin "3") (pinfunction "PC15-OSC32_OUT_3") (pintype "passive"))
      (node (ref "Y1") (pin "1") (pinfunction "1_1") (pintype "passive"))
    )
    (net (code "44") (name "Net-(U1-VBAT)") (class "Default")
      (node (ref "C10") (pin "2") (pinfunction "2_2") (pintype "passive"))
      (node (ref "D12") (pin "1") (pinfunction "1_1") (pintype "passive"))
      (node (ref "J5") (pin "1") (pinfunction "1_1") (pintype "passive"))
      (node (ref "U1") (pin "4") (pinfunction "VBAT_4") (pintype "passive"))
    )
    (net (code "45") (name "Net-(U3-KEY0)") (class "Default")
      (node (ref "R2") (pin "2") (pinfunction "2_2") (pintype "passive"))
      (node (ref "U3") (pin "13") (pinfunction "KEY0_13") (pintype "passive"))
    )
    (net (code "46") (name "Net-(U3-KEY1)") (class "Default")
      (node (ref "R5") (pin "2") (pinfunction "2_2") (pintype "passive"))
      (node (ref "U3") (pin "12") (pinfunction "KEY1_12") (pintype "passive"))
    )
    (net (code "47") (name "Net-(U3-KEY2)") (class "Default")
      (node (ref "R11") (pin "2") (pinfunction "2_2") (pintype "passive"))
      (node (ref "U3") (pin "11") (pinfunction "KEY2_11") (pintype "passive"))
    )
    (net (code "48") (name "Net-(U3-KEY3)") (class "Default")
      (node (ref "R16") (pin "2") (pinfunction "2_2") (pintype "passive"))
      (node (ref "U3") (pin "10") (pinfunction "KEY3_10") (pintype "passive"))
    )
    (net (code "49") (name "Net-(U3-KEY4)") (class "Default")
      (node (ref "R18") (pin "2") (pinfunction "2_2") (pintype "passive"))
      (node (ref "U3") (pin "9") (pinfunction "KEY4_9") (pintype "passive"))
    )
    (net (code "50") (name "Net-(U3-KEY5)") (class "Default")
      (node (ref "R20") (pin "2") (pinfunction "2_2") (pintype "passive"))
      (node (ref "U3") (pin "8") (pinfunction "KEY5_8") (pintype "passive"))
    )
    (net (code "51") (name "Net-(U3-KEY6)") (class "Default")
      (node (ref "R21") (pin "2") (pinfunction "2_2") (pintype "passive"))
      (node (ref "U3") (pin "7") (pinfunction "KEY6_7") (pintype "passive"))
    )
    (net (code "52") (name "Net-(U3-~{CHANGE})") (class "Default")
      (node (ref "R6") (pin "1") (pinfunction "1_1") (pintype "passive"))
      (node (ref "U3") (pin "5") (pinfunction "~{CHANGE}_5") (pintype "passive"))
    )
    (net (code "53") (name "VCC") (class "Default")
      (node (ref "BZ1") (pin "P") (pinfunction "P_P") (pintype "passive"))
      (node (ref "C2") (pin "2") (pinfunction "2_2") (pintype "passive"))
      (node (ref "C3") (pin "2") (pinfunction "2_2") (pintype "passive"))
      (node (ref "C4") (pin "2") (pinfunction "2_2") (pintype "passive"))
      (node (ref "C5") (pin "2") (pinfunction "2_2") (pintype "passive"))
      (node (ref "C8") (pin "2") (pinfunction "2_2") (pintype "passive"))
      (node (ref "C9") (pin "2") (pinfunction "2_2") (pintype "passive"))
      (node (ref "J2") (pin "1") (pinfunction "1_1") (pintype "passive"))
      (node (ref "R10") (pin "2") (pinfunction "2_2") (pintype "passive"))
      (node (ref "R3") (pin "2") (pinfunction "2_2") (pintype "passive"))
      (node (ref "R4") (pin "2") (pinfunction "2_2") (pintype "passive"))
      (node (ref "R6") (pin "2") (pinfunction "2_2") (pintype "passive"))
      (node (ref "R7") (pin "2") (pinfunction "2_2") (pintype "passive"))
      (node (ref "R8") (pin "2") (pinfunction "2_2") (pintype "passive"))
      (node (ref "TP2") (pin "1") (pinfunction "0_1") (pintype "passive"))
      (node (ref "U1") (pin "6") (pinfunction "VDD/VDDA_6") (pintype "passive"))
      (node (ref "U2") (pin "2") (pinfunction "OUT_2") (pintype "passive"))
      (node (ref "U2") (pin "4") (pinfunction "VOUT_4") (pintype "passive"))
      (node (ref "U3") (pin "1") (pinfunction "VDD_1") (pintype "passive"))
    )
    (net (code "54") (name "unconnected-(J2-Pad4)") (class "Default")
      (node (ref "J2") (pin "4") (pinfunction "4_4") (pintype "passive"))
    )
    (net (code "55") (name "unconnected-(SW1-Pad2)") (class "Default")
      (node (ref "SW1") (pin "2") (pinfunction "2_2") (pintype "passive+no_connect"))
    )
    (net (code "56") (name "unconnected-(SW1-Pad4)") (class "Default")
      (node (ref "SW1") (pin "4") (pinfunction "4_4") (pintype "passive+no_connect"))
    )
    (net (code "57") (name "unconnected-(SW2-Pad2)") (class "Default")
      (node (ref "SW2") (pin "2") (pinfunction "2_2") (pintype "passive+no_connect"))
    )
    (net (code "58") (name "unconnected-(SW2-Pad4)") (class "Default")
      (node (ref "SW2") (pin "4") (pinfunction "4_4") (pintype "passive+no_connect"))
    )
    (net (code "59") (name "unconnected-(SW3-Pad2)") (class "Default")
      (node (ref "SW3") (pin "2") (pinfunction "2_2") (pintype "passive+no_connect"))
    )
    (net (code "60") (name "unconnected-(SW3-Pad4)") (class "Default")
      (node (ref "SW3") (pin "4") (pinfunction "4_4") (pintype "passive+no_connect"))
    )
    (net (code "61") (name "unconnected-(SW4-Pad2)") (class "Default")
      (node (ref "SW4") (pin "2") (pinfunction "2_2") (pintype "passive+no_connect"))
    )
    (net (code "62") (name "unconnected-(SW4-Pad4)") (class "Default")
      (node (ref "SW4") (pin "4") (pinfunction "4_4") (pintype "passive+no_connect"))
    )
    (net (code "63") (name "unconnected-(SW5-Pad2)") (class "Default")
      (node (ref "SW5") (pin "2") (pinfunction "2_2") (pintype "passive+no_connect"))
    )
    (net (code "64") (name "unconnected-(SW5-Pad4)") (class "Default")
      (node (ref "SW5") (pin "4") (pinfunction "4_4") (pintype "passive+no_connect"))
    )
    (net (code "65") (name "unconnected-(U1-PA1-Pad12)") (class "Default")
      (node (ref "U1") (pin "12") (pinfunction "PA1_12") (pintype "passive"))
    )
    (net (code "66") (name "unconnected-(U1-PA3-Pad14)") (class "Default")
      (node (ref "U1") (pin "14") (pinfunction "PA3_14") (pintype "passive"))
    )
    (net (code "67") (name "unconnected-(U1-PA5-Pad16)") (class "Default")
      (node (ref "U1") (pin "16") (pinfunction "PA5_16") (pintype "passive"))
    )
    (net (code "68") (name "unconnected-(U1-PA6-Pad17)") (class "Default")
      (node (ref "U1") (pin "17") (pinfunction "PA6_17") (pintype "passive"))
    )
    (net (code "69") (name "unconnected-(U1-PA7-Pad18)") (class "Default")
      (node (ref "U1") (pin "18") (pinfunction "PA7_18") (pintype "passive"))
    )
    (net (code "70") (name "unconnected-(U1-PB0-Pad19)") (class "Default")
      (node (ref "U1") (pin "19") (pinfunction "PB0_19") (pintype "passive"))
    )
    (net (code "71") (name "unconnected-(U1-PB1-Pad20)") (class "Default")
      (node (ref "U1") (pin "20") (pinfunction "PB1_20") (pintype "passive"))
    )
    (net (code "72") (name "unconnected-(U1-PB2-Pad21)") (class "Default")
      (node (ref "U1") (pin "21") (pinfunction "PB2_21") (pintype "passive"))
    )
    (net (code "73") (name "unconnected-(U1-PB3-Pad42)") (class "Default")
      (node (ref "U1") (pin "42") (pinfunction "PB3_42") (pintype "passive"))
    )
    (net (code "74") (name "unconnected-(U1-PB4-Pad43)") (class "Default")
      (node (ref "U1") (pin "43") (pinfunction "PB4_43") (pintype "passive"))
    )
    (net (code "75") (name "unconnected-(U1-PB5-Pad44)") (class "Default")
      (node (ref "U1") (pin "44") (pinfunction "PB5_44") (pintype "passive"))
    )
    (net (code "76") (name "unconnected-(U1-PB9-Pad48)") (class "Default")
      (node (ref "U1") (pin "48") (pinfunction "PB9_48") (pintype "passive"))
    )
    (net (code "77") (name "unconnected-(U1-PB10-Pad22)") (class "Default")
      (node (ref "U1") (pin "22") (pinfunction "PB10_22") (pintype "passive"))
    )
    (net (code "78") (name "unconnected-(U1-PB11-Pad23)") (class "Default")
      (node (ref "U1") (pin "23") (pinfunction "PB11_23") (pintype "passive"))
    )
    (net (code "79") (name "unconnected-(U1-PB12-Pad24)") (class "Default")
      (node (ref "U1") (pin "24") (pinfunction "PB12_24") (pintype "passive"))
    )
    (net (code "80") (name "unconnected-(U1-PB13-Pad25)") (class "Default")
      (node (ref "U1") (pin "25") (pinfunction "PB13_25") (pintype "passive"))
    )
    (net (code "81") (name "unconnected-(U1-PB14-Pad26)") (class "Default")
      (node (ref "U1") (pin "26") (pinfunction "PB14_26") (pintype "passive"))
    )
    (net (code "82") (name "unconnected-(U1-PB15-Pad27)") (class "Default")
      (node (ref "U1") (pin "27") (pinfunction "PB15_27") (pintype "passive"))
    )
    (net (code "83") (name "unconnected-(U1-PC13-Pad1)") (class "Default")
      (node (ref "U1") (pin "1") (pinfunction "PC13_1") (pintype "passive"))
    )
    (net (code "84") (name "unconnected-(U1-PF0-OSC_IN-Pad8)") (class "Default")
      (node (ref "U1") (pin "8") (pinfunction "PF0-OSC_IN_8") (pintype "passive"))
    )
    (net (code "85") (name "unconnected-(U1-PF1-OSC_OUT-Pad9)") (class "Default")
      (node (ref "U1") (pin "9") (pinfunction "PF1-OSC_OUT_9") (pintype "passive"))
    )
    (net (code "86") (name "unconnected-(U1-VREF+-Pad5)") (class "Default")
      (node (ref "U1") (pin "5") (pinfunction "VREF+_5") (pintype "passive"))
    )
  )
)
